# SVPXFMC_Carrier_6U_SOM.net
KiCad netlist of a schematic drawn in Altium Designer
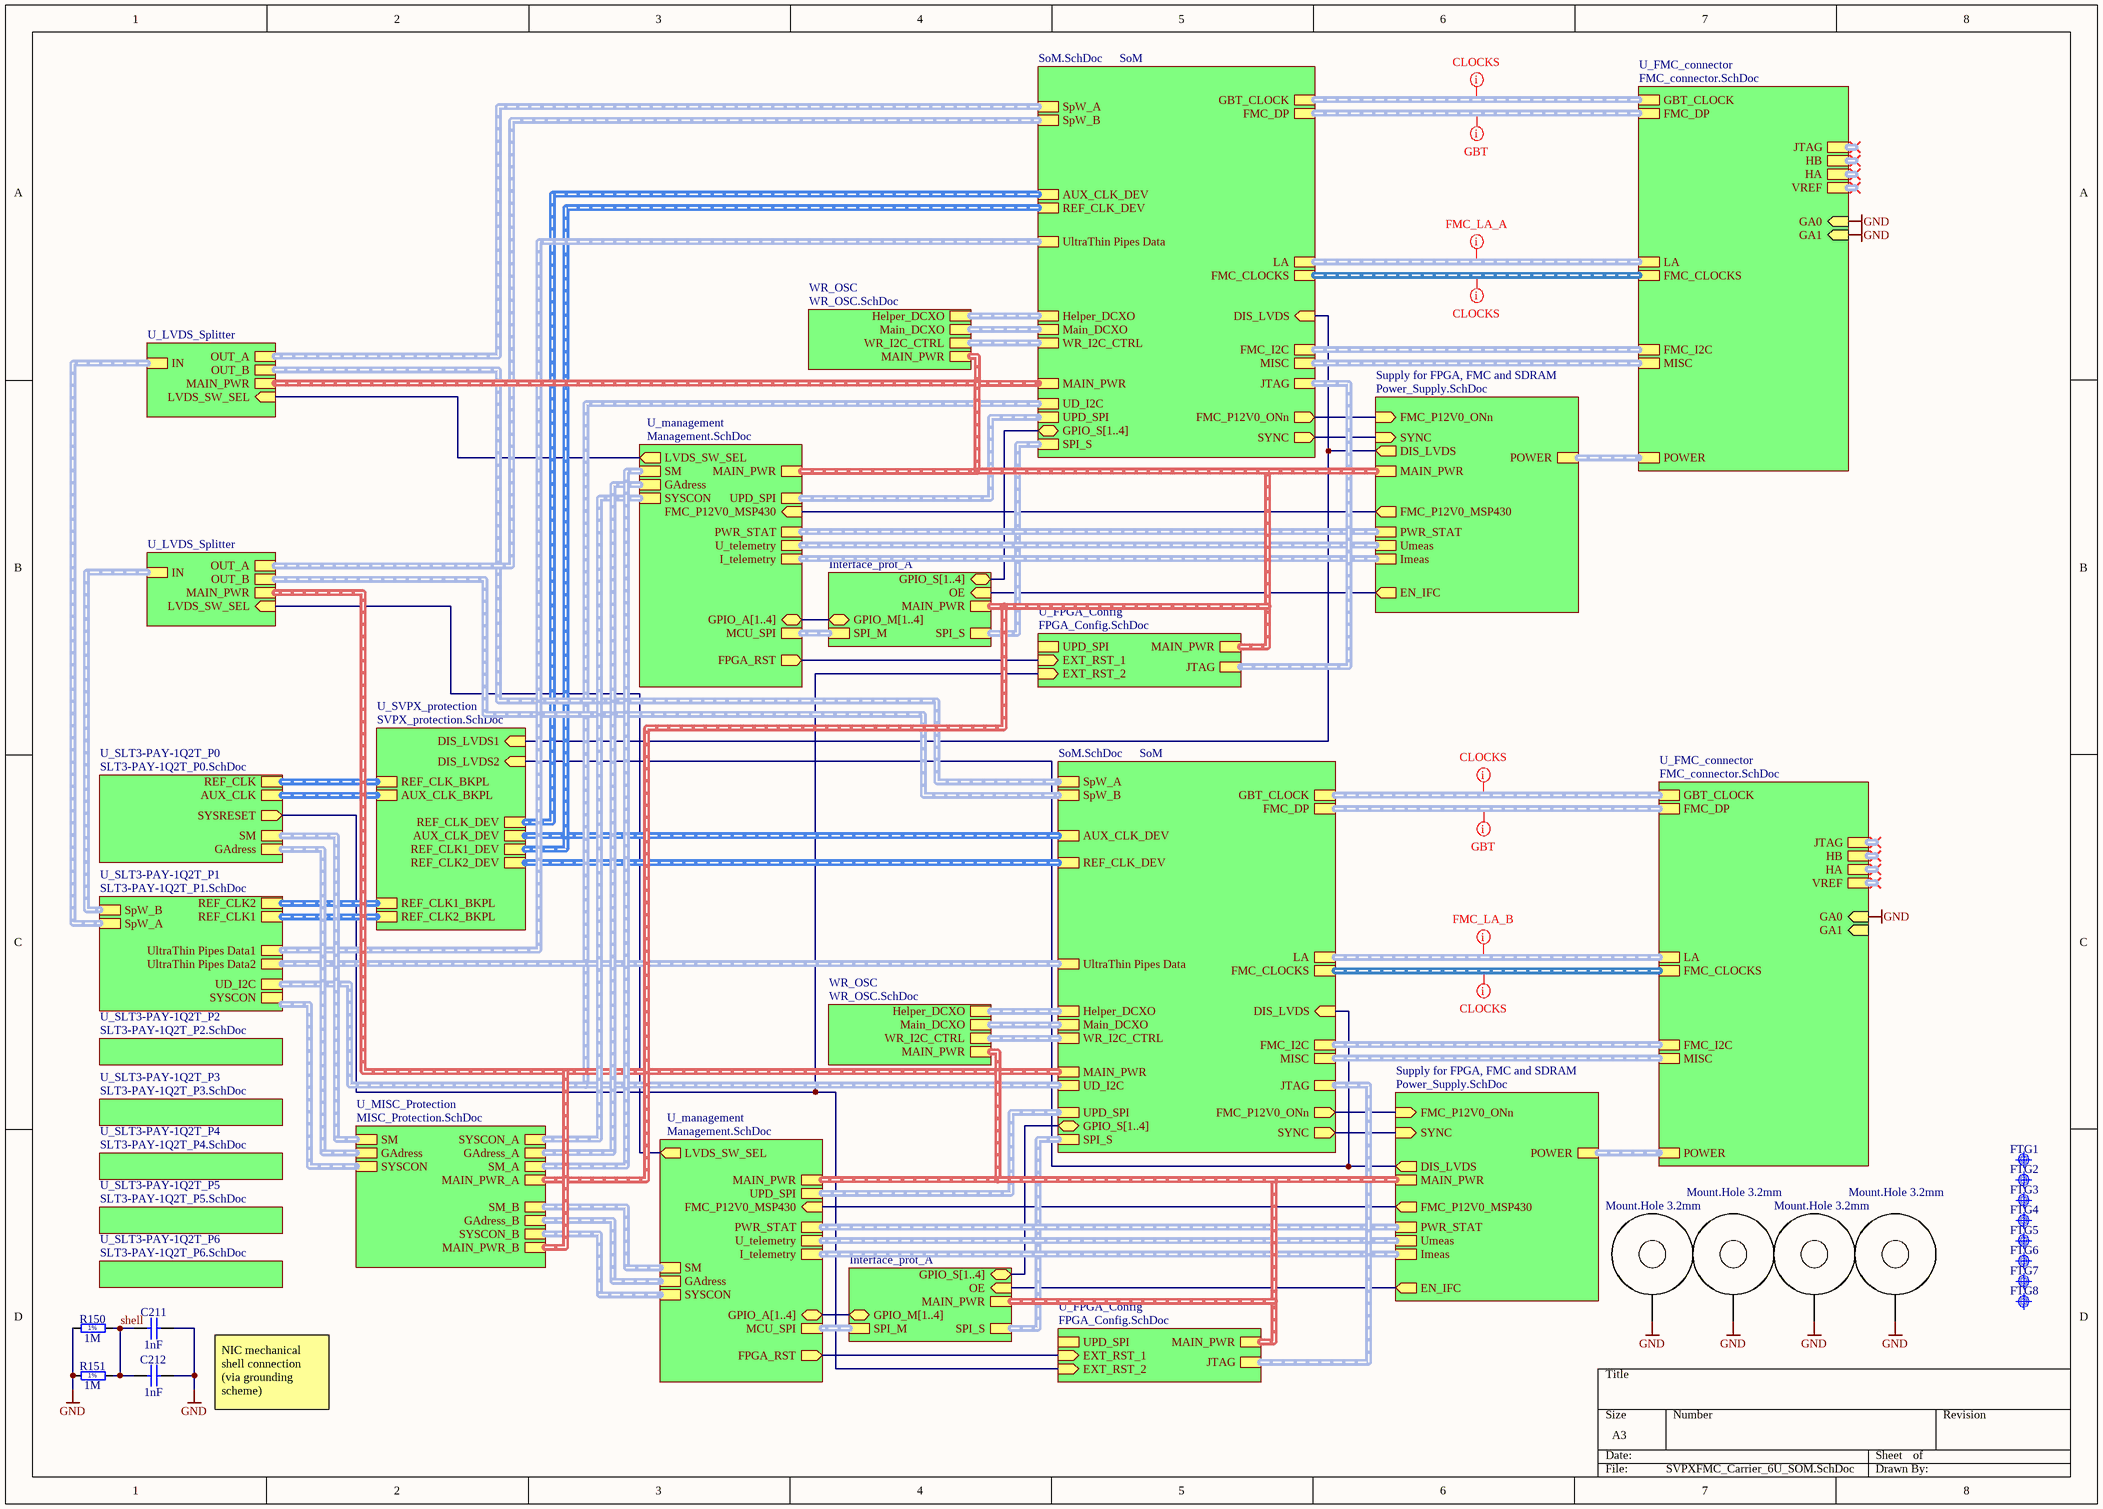
[diagram p0: SVPXFMC_Carrier_6U_SOM.SchDoc]

(export (version "E")
  (design (tool "Eeschema 10.0.6"))
  (components
    (comp (ref "C211")
      (value "1nF")
      (footprint "CAPC1005X55N")
      (description "Non-polarised capacitor")
      (fields
        (field (name "PART NUMBER") "CC0402_1NF_50V_10%_X7R")
        (field (name "VOLTAGE") "50V")
        (field (name "AUTHOR") "CERN DEM JLC")
      )
      (libsource (lib "Capacitors") (part "Capacitor - non polarized"))
    )
    (comp (ref "C212")
      (value "1nF")
      (footprint "CAPC1005X55N")
      (description "Non-polarised capacitor")
      (fields
        (field (name "PART NUMBER") "CC0402_1NF_50V_10%_X7R")
        (field (name "VOLTAGE") "50V")
        (field (name "AUTHOR") "CERN DEM JLC")
      )
      (libsource (lib "Capacitors") (part "Capacitor - non polarized"))
    )
    (comp (ref "FTG1")
      (value "Use only in PCB")
      (footprint "FIDUCIAL_TOP_C100-200")
      (description "Fiducial Target")
      (fields (field (name "PART NUMBER") "FIDUCIAL_TARGET_C100-200") (field (name "AUTHOR") "CERN DEM JLC"))
      (libsource (lib "Eletro-mechanical") (part "Fiducial Target"))
    )
    (comp (ref "FTG2")
      (value "Use only in PCB")
      (footprint "FIDUCIAL_TOP_C100-200")
      (description "Fiducial Target")
      (fields (field (name "PART NUMBER") "FIDUCIAL_TARGET_C100-200") (field (name "AUTHOR") "CERN DEM JLC"))
      (libsource (lib "Eletro-mechanical") (part "Fiducial Target"))
    )
    (comp (ref "FTG3")
      (value "Use only in PCB")
      (footprint "FIDUCIAL_TOP_C100-200")
      (description "Fiducial Target")
      (fields (field (name "PART NUMBER") "FIDUCIAL_TARGET_C100-200") (field (name "AUTHOR") "CERN DEM JLC"))
      (libsource (lib "Eletro-mechanical") (part "Fiducial Target"))
    )
    (comp (ref "FTG4")
      (value "Use only in PCB")
      (footprint "FIDUCIAL_TOP_C100-200")
      (description "Fiducial Target")
      (fields (field (name "PART NUMBER") "FIDUCIAL_TARGET_C100-200") (field (name "AUTHOR") "CERN DEM JLC"))
      (libsource (lib "Eletro-mechanical") (part "Fiducial Target"))
    )
    (comp (ref "FTG5")
      (value "Use only in PCB")
      (footprint "FIDUCIAL_TOP_C100-200")
      (description "Fiducial Target")
      (fields (field (name "PART NUMBER") "FIDUCIAL_TARGET_C100-200") (field (name "AUTHOR") "CERN DEM JLC"))
      (libsource (lib "Eletro-mechanical") (part "Fiducial Target"))
    )
    (comp (ref "FTG6")
      (value "Use only in PCB")
      (footprint "FIDUCIAL_TOP_C100-200")
      (description "Fiducial Target")
      (fields (field (name "PART NUMBER") "FIDUCIAL_TARGET_C100-200") (field (name "AUTHOR") "CERN DEM JLC"))
      (libsource (lib "Eletro-mechanical") (part "Fiducial Target"))
    )
    (comp (ref "FTG7")
      (value "Use only in PCB")
      (footprint "FIDUCIAL_TOP_C100-200")
      (description "Fiducial Target")
      (fields (field (name "PART NUMBER") "FIDUCIAL_TARGET_C100-200") (field (name "AUTHOR") "CERN DEM JLC"))
      (libsource (lib "Eletro-mechanical") (part "Fiducial Target"))
    )
    (comp (ref "FTG8")
      (value "Use only in PCB")
      (footprint "FIDUCIAL_TOP_C100-200")
      (description "Fiducial Target")
      (fields (field (name "PART NUMBER") "FIDUCIAL_TARGET_C100-200") (field (name "AUTHOR") "CERN DEM JLC"))
      (libsource (lib "Eletro-mechanical") (part "Fiducial Target"))
    )
    (comp (ref "H5")
      (value "Mount.Hole 3.2mm")
      (footprint "MHole3_2mm")
      (libsource (lib "TE") (part "MHole"))
    )
    (comp (ref "H6")
      (value "Mount.Hole 3.2mm")
      (footprint "MHole3_2mm")
      (libsource (lib "TE") (part "MHole"))
    )
    (comp (ref "H7")
      (value "Mount.Hole 3.2mm")
      (footprint "MHole3_2mm")
      (libsource (lib "TE") (part "MHole"))
    )
    (comp (ref "H8")
      (value "Mount.Hole 3.2mm")
      (footprint "MHole3_2mm")
      (libsource (lib "TE") (part "MHole"))
    )
    (comp (ref "R150")
      (value "1M")
      (footprint "RESC1005X40N")
      (description "Resistor - 1%")
      (fields
        (field (name "PART NUMBER") "R0402_1M_1%_0.0625W_100PPM")
        (field (name "POWER") "0.0625W")
        (field (name "AUTHOR") "CERN DEM JLC")
      )
      (libsource (lib "Resistors") (part "Resistor - 1%"))
    )
    (comp (ref "R151")
      (value "1M")
      (footprint "RESC1005X40N")
      (description "Resistor - 1%")
      (fields
        (field (name "PART NUMBER") "R0402_1M_1%_0.0625W_100PPM")
        (field (name "POWER") "0.0625W")
        (field (name "AUTHOR") "CERN DEM JLC")
      )
      (libsource (lib "Resistors") (part "Resistor - 1%"))
    )
  )
  (nets
    (net (code "94") (name "/shell") (class "Default")
      (node (ref "C211") (pin "1") (pinfunction "1_1") (pintype "passive"))
      (node (ref "C212") (pin "1") (pinfunction "1_1") (pintype "passive"))
      (node (ref "R150") (pin "2") (pinfunction "2_2") (pintype "passive"))
      (node (ref "R151") (pin "2") (pinfunction "2_2") (pintype "passive"))
    )
    (net (code "95") (name "GND") (class "Default")
      (node (ref "C211") (pin "2") (pinfunction "2_2") (pintype "passive"))
      (node (ref "C212") (pin "2") (pinfunction "2_2") (pintype "passive"))
      (node (ref "H5") (pin "1") (pinfunction "1_1") (pintype "passive"))
      (node (ref "H6") (pin "1") (pinfunction "1_1") (pintype "passive"))
      (node (ref "H7") (pin "1") (pinfunction "1_1") (pintype "passive"))
      (node (ref "H8") (pin "1") (pinfunction "1_1") (pintype "passive"))
      (node (ref "R150") (pin "1") (pinfunction "1_1") (pintype "passive"))
      (node (ref "R151") (pin "1") (pinfunction "1_1") (pintype "passive"))
    )
  )
)
